# EAGLE.net
KiCad netlist of a schematic drawn in EAGLE
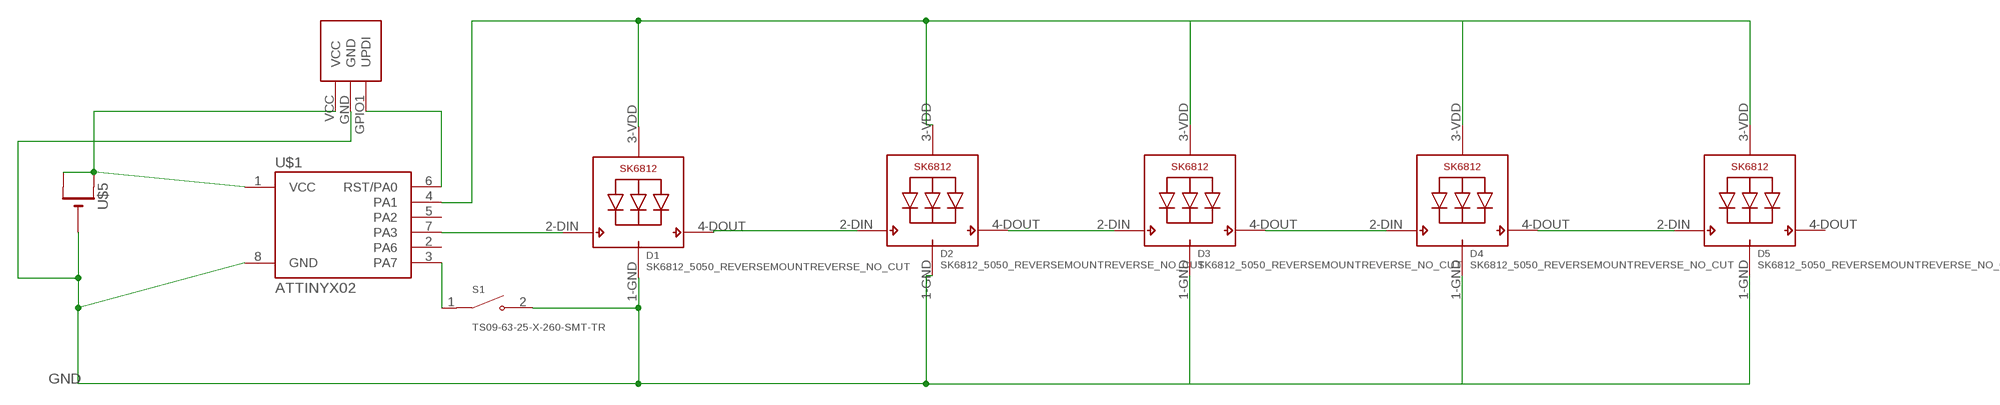
[diagram p0: schematic, sheet 1]

(export (version "E")
  (design (tool "Eeschema 10.0.6"))
  (components
    (comp (ref "D1")
      (value "SK6812_5050_REVERSEMOUNTREVERSE_NO_CUT")
      (footprint "eagle-import:SK6812_REVERSE_NO_CUT")
      (libsource (lib "eagle-import") (part "SK6812_5050_REVERSEMOUNTREVERSE_NO_CUT"))
    )
    (comp (ref "D2")
      (value "SK6812_5050_REVERSEMOUNTREVERSE_NO_CUT")
      (footprint "eagle-import:SK6812_REVERSE_NO_CUT")
      (libsource (lib "eagle-import") (part "SK6812_5050_REVERSEMOUNTREVERSE_NO_CUT"))
    )
    (comp (ref "D3")
      (value "SK6812_5050_REVERSEMOUNTREVERSE_NO_CUT")
      (footprint "eagle-import:SK6812_REVERSE_NO_CUT")
      (libsource (lib "eagle-import") (part "SK6812_5050_REVERSEMOUNTREVERSE_NO_CUT"))
    )
    (comp (ref "D4")
      (value "SK6812_5050_REVERSEMOUNTREVERSE_NO_CUT")
      (footprint "eagle-import:SK6812_REVERSE_NO_CUT")
      (libsource (lib "eagle-import") (part "SK6812_5050_REVERSEMOUNTREVERSE_NO_CUT"))
    )
    (comp (ref "D5")
      (value "SK6812_5050_REVERSEMOUNTREVERSE_NO_CUT")
      (footprint "eagle-import:SK6812_REVERSE_NO_CUT")
      (libsource (lib "eagle-import") (part "SK6812_5050_REVERSEMOUNTREVERSE_NO_CUT"))
    )
    (comp (ref "S1")
      (value "TS09-63-25-X-260-SMT-TR")
      (footprint "eagle-import:SW_TS09-63-25-X-260-SMT-TR")
      (fields (field (name "MANUFACTURER") "CUI Devices"))
      (libsource (lib "eagle-import") (part "TS09-63-25-X-260-SMT-TR"))
    )
    (comp (ref "U$1")
      (value "ATTINYX02")
      (footprint "eagle-import:SOIC08_JEDEC_150MIL")
      (libsource (lib "eagle-import") (part "ATTINYX02"))
    )
    (comp (ref "U$2")
      (value "SAO")
      (footprint "eagle-import:SAO_SMD")
      (libsource (lib "eagle-import") (part "SAO"))
    )
    (comp (ref "U$5")
      (value "CR2032SMT")
      (footprint "eagle-import:CR2032-SMD")
      (libsource (lib "eagle-import") (part "CR2032SMT"))
    )
  )
  (nets
    (net (code "1") (name "/GND") (class "Default")
      (node (ref "D1") (pin "1-GND") (pinfunction "GND_1-GND") (pintype "power_in"))
      (node (ref "D2") (pin "1-GND") (pinfunction "GND_1-GND") (pintype "power_in"))
      (node (ref "D3") (pin "1-GND") (pinfunction "GND_1-GND") (pintype "power_in"))
      (node (ref "D4") (pin "1-GND") (pinfunction "GND_1-GND") (pintype "power_in"))
      (node (ref "D5") (pin "1-GND") (pinfunction "GND_1-GND") (pintype "power_in"))
      (node (ref "S1") (pin "2") (pinfunction "2_2") (pintype "passive"))
      (node (ref "U$1") (pin "8") (pinfunction "GND_8") (pintype "power_in"))
      (node (ref "U$2") (pin "GND") (pinfunction "GND_GND") (pintype "bidirectional"))
      (node (ref "U$5") (pin "-") (pinfunction "-_-") (pintype "passive"))
    )
    (net (code "2") (name "Net-(D1-DI)") (class "Default")
      (node (ref "D1") (pin "2-DIN") (pinfunction "DI_2-DIN") (pintype "input"))
      (node (ref "U$1") (pin "7") (pinfunction "PA3_7") (pintype "bidirectional"))
    )
    (net (code "3") (name "Net-(D1-DO)") (class "Default")
      (node (ref "D1") (pin "4-DOUT") (pinfunction "DO_4-DOUT") (pintype "output"))
      (node (ref "D2") (pin "2-DIN") (pinfunction "DI_2-DIN") (pintype "input"))
    )
    (net (code "4") (name "Net-(D1-VDD)") (class "Default")
      (node (ref "D1") (pin "3-VDD") (pinfunction "VDD_3-VDD") (pintype "power_in"))
      (node (ref "D2") (pin "3-VDD") (pinfunction "VDD_3-VDD") (pintype "power_in"))
      (node (ref "D3") (pin "3-VDD") (pinfunction "VDD_3-VDD") (pintype "power_in"))
      (node (ref "D4") (pin "3-VDD") (pinfunction "VDD_3-VDD") (pintype "power_in"))
      (node (ref "D5") (pin "3-VDD") (pinfunction "VDD_3-VDD") (pintype "power_in"))
      (node (ref "U$1") (pin "4") (pinfunction "PA1_4") (pintype "bidirectional"))
    )
    (net (code "5") (name "Net-(D2-DO)") (class "Default")
      (node (ref "D2") (pin "4-DOUT") (pinfunction "DO_4-DOUT") (pintype "output"))
      (node (ref "D3") (pin "2-DIN") (pinfunction "DI_2-DIN") (pintype "input"))
    )
    (net (code "6") (name "Net-(D3-DO)") (class "Default")
      (node (ref "D3") (pin "4-DOUT") (pinfunction "DO_4-DOUT") (pintype "output"))
      (node (ref "D4") (pin "2-DIN") (pinfunction "DI_2-DIN") (pintype "input"))
    )
    (net (code "7") (name "Net-(D4-DO)") (class "Default")
      (node (ref "D4") (pin "4-DOUT") (pinfunction "DO_4-DOUT") (pintype "output"))
      (node (ref "D5") (pin "2-DIN") (pinfunction "DI_2-DIN") (pintype "input"))
    )
    (net (code "8") (name "Net-(U$1-PA7)") (class "Default")
      (node (ref "S1") (pin "1") (pinfunction "1_1") (pintype "passive"))
      (node (ref "U$1") (pin "3") (pinfunction "PA7_3") (pintype "bidirectional"))
    )
    (net (code "9") (name "Net-(U$1-RST{slash}PA0)") (class "Default")
      (node (ref "U$1") (pin "6") (pinfunction "RST/PA0_6") (pintype "bidirectional"))
      (node (ref "U$2") (pin "GPIO1") (pinfunction "UPDI_GPIO1") (pintype "bidirectional"))
    )
    (net (code "10") (name "Net-(U$1-VCC)") (class "Default")
      (node (ref "U$1") (pin "1") (pinfunction "VCC_1") (pintype "power_in"))
      (node (ref "U$2") (pin "VCC") (pinfunction "VCC_VCC") (pintype "bidirectional"))
      (node (ref "U$5") (pin "+$1") (pinfunction "+_+$1") (pintype "passive"))
      (node (ref "U$5") (pin "+$2") (pinfunction "+1_+$2") (pintype "passive"))
    )
    (net (code "11") (name "unconnected-(D5-DO-Pad4-DOUT)") (class "Default")
      (node (ref "D5") (pin "4-DOUT") (pinfunction "DO_4-DOUT") (pintype "output"))
    )
    (net (code "12") (name "unconnected-(U$1-PA2-Pad5)") (class "Default")
      (node (ref "U$1") (pin "5") (pinfunction "PA2_5") (pintype "bidirectional"))
    )
    (net (code "13") (name "unconnected-(U$1-PA6-Pad2)") (class "Default")
      (node (ref "U$1") (pin "2") (pinfunction "PA6_2") (pintype "bidirectional"))
    )
  )
)
